# rs232.net
KiCad netlist of a schematic drawn in EAGLE
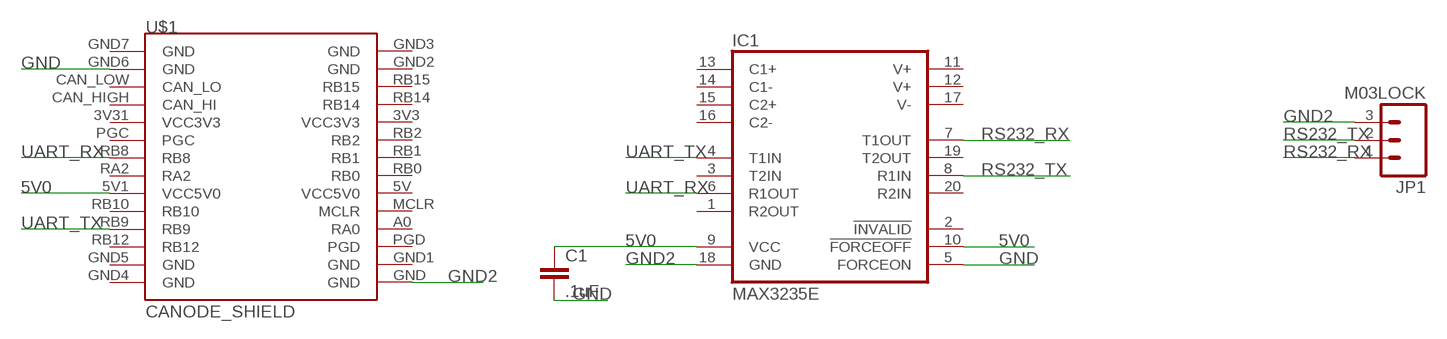
[diagram p0: schematic, sheet 1]

(export (version "E")
  (design (tool "Eeschema 10.0.6"))
  (components
    (comp (ref "C1")
      (value ".1uF")
      (footprint "eagle-import:1206")
      (libsource (lib "eagle-import") (part "CAP1206"))
    )
    (comp (ref "IC1")
      (value "MAX3235E")
      (footprint "eagle-import:SO20L")
      (fields (field (name "MF") "MAXIM"))
      (libsource (lib "eagle-import") (part "MAX3235E"))
    )
    (comp (ref "JP1")
      (value "M03LOCK")
      (footprint "eagle-import:1X03_LOCK")
      (libsource (lib "eagle-import") (part "M03LOCK"))
    )
    (comp (ref "U$1")
      (value "CANODE_SHIELD")
      (footprint "eagle-import:CANODE_SHIELD")
      (libsource (lib "eagle-import") (part "CANODE_SHIELD"))
    )
  )
  (nets
    (net (code "1") (name "/5V0") (class "Default")
      (node (ref "C1") (pin "1") (pinfunction "1_1") (pintype "passive"))
      (node (ref "IC1") (pin "10") (pinfunction "~{FORCEOFF}_10") (pintype "input"))
      (node (ref "IC1") (pin "9") (pinfunction "VCC_9") (pintype "power_in"))
      (node (ref "U$1") (pin "5V1") (pinfunction "VCC5V0_5V1") (pintype "bidirectional"))
    )
    (net (code "2") (name "/GND") (class "Default")
      (node (ref "C1") (pin "2") (pinfunction "2_2") (pintype "passive"))
      (node (ref "IC1") (pin "5") (pinfunction "FORCEON_5") (pintype "input"))
      (node (ref "U$1") (pin "GND6") (pinfunction "GND_GND6") (pintype "bidirectional"))
    )
    (net (code "3") (name "/GND2") (class "Default")
      (node (ref "IC1") (pin "18") (pinfunction "GND_18") (pintype "power_in"))
      (node (ref "JP1") (pin "3") (pinfunction "3_3") (pintype "passive"))
      (node (ref "U$1") (pin "GND") (pinfunction "GND_GND") (pintype "bidirectional"))
    )
    (net (code "4") (name "/RS232_RX") (class "Default")
      (node (ref "IC1") (pin "7") (pinfunction "T1OUT_7") (pintype "output"))
      (node (ref "JP1") (pin "1") (pinfunction "1_1") (pintype "passive"))
    )
    (net (code "5") (name "/RS232_TX") (class "Default")
      (node (ref "IC1") (pin "8") (pinfunction "R1IN_8") (pintype "input"))
      (node (ref "JP1") (pin "2") (pinfunction "2_2") (pintype "passive"))
    )
    (net (code "6") (name "/UART_RX") (class "Default")
      (node (ref "IC1") (pin "6") (pinfunction "R1OUT_6") (pintype "output"))
      (node (ref "U$1") (pin "RB8") (pinfunction "RB8_RB8") (pintype "bidirectional"))
    )
    (net (code "7") (name "/UART_TX") (class "Default")
      (node (ref "IC1") (pin "4") (pinfunction "T1IN_4") (pintype "input"))
      (node (ref "U$1") (pin "RB9") (pinfunction "RB9_RB9") (pintype "bidirectional"))
    )
    (net (code "8") (name "unconnected-(IC1-C1+-Pad13)") (class "Default")
      (node (ref "IC1") (pin "13") (pinfunction "C1+_13") (pintype "passive"))
    )
    (net (code "9") (name "unconnected-(IC1-C1--Pad14)") (class "Default")
      (node (ref "IC1") (pin "14") (pinfunction "C1-_14") (pintype "passive"))
    )
    (net (code "10") (name "unconnected-(IC1-C2+-Pad15)") (class "Default")
      (node (ref "IC1") (pin "15") (pinfunction "C2+_15") (pintype "passive"))
    )
    (net (code "11") (name "unconnected-(IC1-C2--Pad16)") (class "Default")
      (node (ref "IC1") (pin "16") (pinfunction "C2-_16") (pintype "passive"))
    )
    (net (code "12") (name "unconnected-(IC1-R2IN-Pad20)") (class "Default")
      (node (ref "IC1") (pin "20") (pinfunction "R2IN_20") (pintype "input"))
    )
    (net (code "13") (name "unconnected-(IC1-R2OUT-Pad1)") (class "Default")
      (node (ref "IC1") (pin "1") (pinfunction "R2OUT_1") (pintype "output"))
    )
    (net (code "14") (name "unconnected-(IC1-T2IN-Pad3)") (class "Default")
      (node (ref "IC1") (pin "3") (pinfunction "T2IN_3") (pintype "input"))
    )
    (net (code "15") (name "unconnected-(IC1-T2OUT-Pad19)") (class "Default")
      (node (ref "IC1") (pin "19") (pinfunction "T2OUT_19") (pintype "output"))
    )
    (net (code "16") (name "unconnected-(IC1-V+-Pad11)") (class "Default")
      (node (ref "IC1") (pin "11") (pinfunction "V+_11") (pintype "passive"))
    )
    (net (code "17") (name "unconnected-(IC1-V+-Pad12)") (class "Default")
      (node (ref "IC1") (pin "12") (pinfunction "V+_12") (pintype "passive"))
    )
    (net (code "18") (name "unconnected-(IC1-V--Pad17)") (class "Default")
      (node (ref "IC1") (pin "17") (pinfunction "V-_17") (pintype "passive"))
    )
    (net (code "19") (name "unconnected-(IC1-~{INVALID}-Pad2)") (class "Default")
      (node (ref "IC1") (pin "2") (pinfunction "~{INVALID}_2") (pintype "output"))
    )
    (net (code "20") (name "unconnected-(U$1-CAN_HI-PadCAN_HIGH)") (class "Default")
      (node (ref "U$1") (pin "CAN_HIGH") (pinfunction "CAN_HI_CAN_HIGH") (pintype "bidirectional"))
    )
    (net (code "21") (name "unconnected-(U$1-CAN_LO-PadCAN_LOW)") (class "Default")
      (node (ref "U$1") (pin "CAN_LOW") (pinfunction "CAN_LO_CAN_LOW") (pintype "bidirectional"))
    )
    (net (code "22") (name "unconnected-(U$1-GND-PadGND1)") (class "Default")
      (node (ref "U$1") (pin "GND1") (pinfunction "GND_GND1") (pintype "bidirectional"))
    )
    (net (code "23") (name "unconnected-(U$1-GND-PadGND2)") (class "Default")
      (node (ref "U$1") (pin "GND2") (pinfunction "GND_GND2") (pintype "bidirectional"))
    )
    (net (code "24") (name "unconnected-(U$1-GND-PadGND3)") (class "Default")
      (node (ref "U$1") (pin "GND3") (pinfunction "GND_GND3") (pintype "bidirectional"))
    )
    (net (code "25") (name "unconnected-(U$1-GND-PadGND4)") (class "Default")
      (node (ref "U$1") (pin "GND4") (pinfunction "GND_GND4") (pintype "bidirectional"))
    )
    (net (code "26") (name "unconnected-(U$1-GND-PadGND5)") (class "Default")
      (node (ref "U$1") (pin "GND5") (pinfunction "GND_GND5") (pintype "bidirectional"))
    )
    (net (code "27") (name "unconnected-(U$1-GND-PadGND7)") (class "Default")
      (node (ref "U$1") (pin "GND7") (pinfunction "GND_GND7") (pintype "bidirectional"))
    )
    (net (code "28") (name "unconnected-(U$1-PadMCLR)") (class "Default")
      (node (ref "U$1") (pin "MCLR") (pinfunction "MCLR_MCLR") (pintype "bidirectional"))
    )
    (net (code "29") (name "unconnected-(U$1-PadPGC)") (class "Default")
      (node (ref "U$1") (pin "PGC") (pinfunction "PGC_PGC") (pintype "bidirectional"))
    )
    (net (code "30") (name "unconnected-(U$1-PadPGD)") (class "Default")
      (node (ref "U$1") (pin "PGD") (pinfunction "PGD_PGD") (pintype "bidirectional"))
    )
    (net (code "31") (name "unconnected-(U$1-PadRA2)") (class "Default")
      (node (ref "U$1") (pin "RA2") (pinfunction "RA2_RA2") (pintype "bidirectional"))
    )
    (net (code "32") (name "unconnected-(U$1-PadRB0)") (class "Default")
      (node (ref "U$1") (pin "RB0") (pinfunction "RB0_RB0") (pintype "bidirectional"))
    )
    (net (code "33") (name "unconnected-(U$1-PadRB1)") (class "Default")
      (node (ref "U$1") (pin "RB1") (pinfunction "RB1_RB1") (pintype "bidirectional"))
    )
    (net (code "34") (name "unconnected-(U$1-PadRB2)") (class "Default")
      (node (ref "U$1") (pin "RB2") (pinfunction "RB2_RB2") (pintype "bidirectional"))
    )
    (net (code "35") (name "unconnected-(U$1-PadRB10)") (class "Default")
      (node (ref "U$1") (pin "RB10") (pinfunction "RB10_RB10") (pintype "bidirectional"))
    )
    (net (code "36") (name "unconnected-(U$1-PadRB12)") (class "Default")
      (node (ref "U$1") (pin "RB12") (pinfunction "RB12_RB12") (pintype "bidirectional"))
    )
    (net (code "37") (name "unconnected-(U$1-PadRB14)") (class "Default")
      (node (ref "U$1") (pin "RB14") (pinfunction "RB14_RB14") (pintype "bidirectional"))
    )
    (net (code "38") (name "unconnected-(U$1-PadRB15)") (class "Default")
      (node (ref "U$1") (pin "RB15") (pinfunction "RB15_RB15") (pintype "bidirectional"))
    )
    (net (code "39") (name "unconnected-(U$1-RA0-PadA0)") (class "Default")
      (node (ref "U$1") (pin "A0") (pinfunction "RA0_A0") (pintype "bidirectional"))
    )
    (net (code "40") (name "unconnected-(U$1-VCC3V3-Pad3V3)") (class "Default")
      (node (ref "U$1") (pin "3V3") (pinfunction "VCC3V3_3V3") (pintype "bidirectional"))
    )
    (net (code "41") (name "unconnected-(U$1-VCC3V3-Pad3V31)") (class "Default")
      (node (ref "U$1") (pin "3V31") (pinfunction "VCC3V3_3V31") (pintype "bidirectional"))
    )
    (net (code "42") (name "unconnected-(U$1-VCC5V0-Pad5V)") (class "Default")
      (node (ref "U$1") (pin "5V") (pinfunction "VCC5V0_5V") (pintype "bidirectional"))
    )
  )
)
